# Fujin_Encoder.net
KiCad netlist of a schematic drawn in Altium Designer
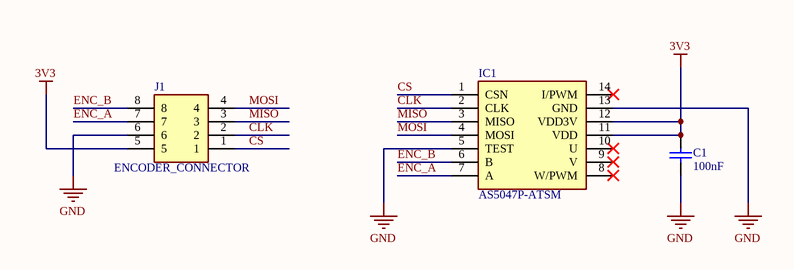
[diagram p0: Fujin_Encoder.SchDoc]

(export (version "E")
  (design (tool "Eeschema 10.0.6"))
  (components
    (comp (ref "C1")
      (value "100nF")
      (footprint "Capacitor-0603")
      (description "Capacitor Cer 100nF 50V")
      (fields (field (name "MANUFACTURER PART NUMBER") "IMP14925"))
      (libsource (lib "EncoderLib") (part "CAP 100NF 50V"))
    )
    (comp (ref "IC1")
      (value "AS5047P-ATSM")
      (footprint "SOP65P640X120-14N")
      (description "Integrated Circuit")
      (fields (field (name "MOUSER PART NUMBER") "985-AS5047P-ATSM"))
      (libsource (lib "EncoderLib") (part "AS5047P-ATSM"))
    )
    (comp (ref "J1")
      (value "ENCODER_CONNECTOR")
      (footprint "ENCODER_CONN")
      (libsource (lib "EncoderLib") (part "ENCODER_CONNECTOR"))
    )
  )
  (nets
    (net (code "1") (name "/CLK") (class "Default")
      (node (ref "IC1") (pin "2") (pinfunction "CLK_2") (pintype "passive"))
      (node (ref "J1") (pin "2") (pinfunction "2_2") (pintype "passive"))
    )
    (net (code "2") (name "/CS") (class "Default")
      (node (ref "IC1") (pin "1") (pinfunction "CSN_1") (pintype "passive"))
      (node (ref "J1") (pin "1") (pinfunction "1_1") (pintype "passive"))
    )
    (net (code "3") (name "/ENC_A") (class "Default")
      (node (ref "IC1") (pin "7") (pinfunction "A_7") (pintype "passive"))
      (node (ref "J1") (pin "7") (pinfunction "7_7") (pintype "passive"))
    )
    (net (code "4") (name "/ENC_B") (class "Default")
      (node (ref "IC1") (pin "6") (pinfunction "B_6") (pintype "passive"))
      (node (ref "J1") (pin "8") (pinfunction "8_8") (pintype "passive"))
    )
    (net (code "5") (name "/MISO") (class "Default")
      (node (ref "IC1") (pin "3") (pinfunction "MISO_3") (pintype "passive"))
      (node (ref "J1") (pin "3") (pinfunction "3_3") (pintype "passive"))
    )
    (net (code "6") (name "/MOSI") (class "Default")
      (node (ref "IC1") (pin "4") (pinfunction "MOSI_4") (pintype "passive"))
      (node (ref "J1") (pin "4") (pinfunction "4_4") (pintype "passive"))
    )
    (net (code "7") (name "3V3") (class "Default")
      (node (ref "C1") (pin "2") (pinfunction "2_2") (pintype "passive"))
      (node (ref "IC1") (pin "11") (pinfunction "VDD_11") (pintype "passive"))
      (node (ref "IC1") (pin "12") (pinfunction "VDD3V_12") (pintype "passive"))
      (node (ref "J1") (pin "5") (pinfunction "5_5") (pintype "passive"))
    )
    (net (code "8") (name "GND") (class "Default")
      (node (ref "C1") (pin "1") (pinfunction "1_1") (pintype "passive"))
      (node (ref "IC1") (pin "13") (pinfunction "GND_13") (pintype "passive"))
      (node (ref "IC1") (pin "5") (pinfunction "TEST_5") (pintype "passive"))
      (node (ref "J1") (pin "6") (pinfunction "6_6") (pintype "passive"))
    )
    (net (code "9") (name "unconnected-(IC1-I{slash}PWM-Pad14)") (class "Default")
      (node (ref "IC1") (pin "14") (pinfunction "I/PWM_14") (pintype "passive+no_connect"))
    )
    (net (code "10") (name "unconnected-(IC1-U-Pad10)") (class "Default")
      (node (ref "IC1") (pin "10") (pinfunction "U_10") (pintype "passive+no_connect"))
    )
    (net (code "11") (name "unconnected-(IC1-V-Pad9)") (class "Default")
      (node (ref "IC1") (pin "9") (pinfunction "V_9") (pintype "passive+no_connect"))
    )
    (net (code "12") (name "unconnected-(IC1-W{slash}PWM-Pad8)") (class "Default")
      (node (ref "IC1") (pin "8") (pinfunction "W/PWM_8") (pintype "passive+no_connect"))
    )
  )
)
